# SCH_POTENCIA.net
KiCad netlist of a schematic drawn in Altium Designer
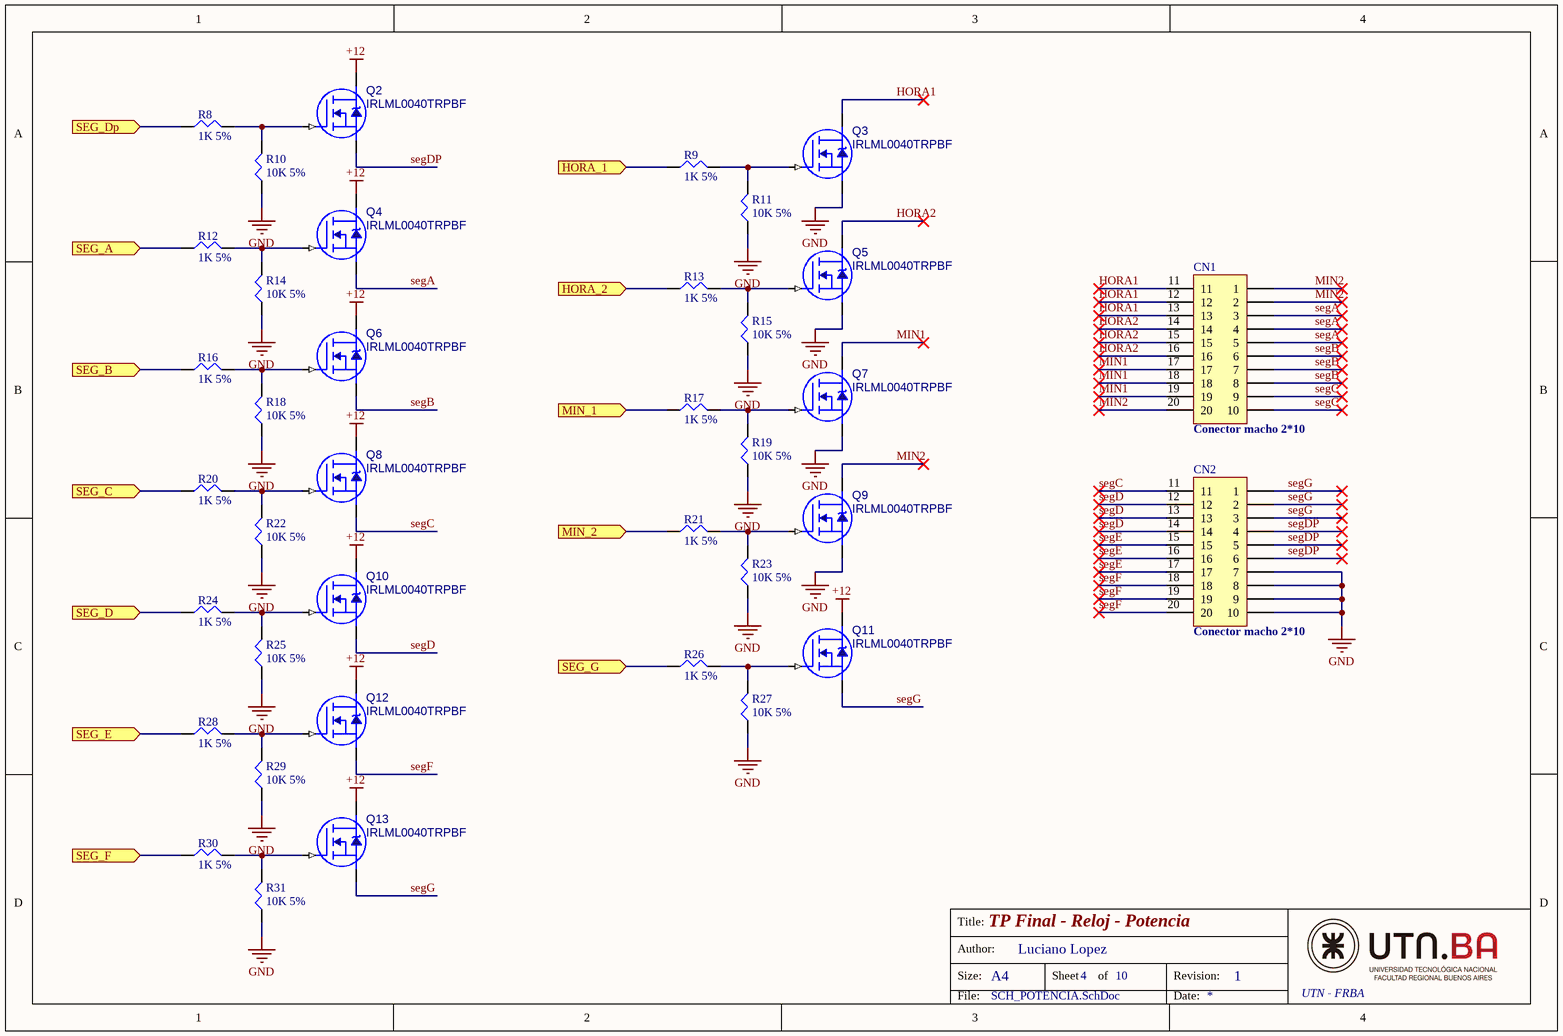
[diagram p0: SCH_POTENCIA.SchDoc]

(export (version "E")
  (design (tool "Eeschema 10.0.6"))
  (components
    (comp (ref "CN1")
      (value "Conector macho 2*10")
      (description "Connector Generic 10 Vias")
      (libsource (lib "SCH_LIB") (part "CONN_2x10P"))
    )
    (comp (ref "CN2")
      (value "Conector macho 2*10")
      (description "Connector Generic 10 Vias")
      (libsource (lib "SCH_LIB") (part "CONN_2x10P"))
    )
    (comp (ref "Q2")
      (value "IRLML0040TRPBF")
      (footprint "IC_SOT-23")
      (description "Mosfet N-Ch")
      (libsource (lib "SCH_LIB") (part "N_MOSFET_SOT23"))
    )
    (comp (ref "Q3")
      (value "IRLML0040TRPBF")
      (footprint "IC_SOT-23")
      (description "Mosfet N-Ch")
      (libsource (lib "SCH_LIB") (part "N_MOSFET_SOT23"))
    )
    (comp (ref "Q4")
      (value "IRLML0040TRPBF")
      (footprint "IC_SOT-23")
      (description "Mosfet N-Ch")
      (libsource (lib "SCH_LIB") (part "N_MOSFET_SOT23"))
    )
    (comp (ref "Q5")
      (value "IRLML0040TRPBF")
      (footprint "IC_SOT-23")
      (description "Mosfet N-Ch")
      (libsource (lib "SCH_LIB") (part "N_MOSFET_SOT23"))
    )
    (comp (ref "Q6")
      (value "IRLML0040TRPBF")
      (footprint "IC_SOT-23")
      (description "Mosfet N-Ch")
      (libsource (lib "SCH_LIB") (part "N_MOSFET_SOT23"))
    )
    (comp (ref "Q7")
      (value "IRLML0040TRPBF")
      (footprint "IC_SOT-23")
      (description "Mosfet N-Ch")
      (libsource (lib "SCH_LIB") (part "N_MOSFET_SOT23"))
    )
    (comp (ref "Q8")
      (value "IRLML0040TRPBF")
      (footprint "IC_SOT-23")
      (description "Mosfet N-Ch")
      (libsource (lib "SCH_LIB") (part "N_MOSFET_SOT23"))
    )
    (comp (ref "Q9")
      (value "IRLML0040TRPBF")
      (footprint "IC_SOT-23")
      (description "Mosfet N-Ch")
      (libsource (lib "SCH_LIB") (part "N_MOSFET_SOT23"))
    )
    (comp (ref "Q10")
      (value "IRLML0040TRPBF")
      (footprint "IC_SOT-23")
      (description "Mosfet N-Ch")
      (libsource (lib "SCH_LIB") (part "N_MOSFET_SOT23"))
    )
    (comp (ref "Q11")
      (value "IRLML0040TRPBF")
      (footprint "IC_SOT-23")
      (description "Mosfet N-Ch")
      (libsource (lib "SCH_LIB") (part "N_MOSFET_SOT23"))
    )
    (comp (ref "Q12")
      (value "IRLML0040TRPBF")
      (footprint "IC_SOT-23")
      (description "Mosfet N-Ch")
      (libsource (lib "SCH_LIB") (part "N_MOSFET_SOT23"))
    )
    (comp (ref "Q13")
      (value "IRLML0040TRPBF")
      (footprint "IC_SOT-23")
      (description "Mosfet N-Ch")
      (libsource (lib "SCH_LIB") (part "N_MOSFET_SOT23"))
    )
    (comp (ref "R8")
      (value "1K 5%")
      (footprint "R_0805")
      (libsource (lib "IDCI_WifiNode_2_R00") (part "Resistor"))
    )
    (comp (ref "R9")
      (value "1K 5%")
      (footprint "R_0805")
      (libsource (lib "IDCI_WifiNode_2_R00") (part "Resistor"))
    )
    (comp (ref "R10")
      (value "10K 5%")
      (footprint "R_0805")
      (libsource (lib "IDCI_WifiNode_2_R00") (part "Resistor"))
    )
    (comp (ref "R11")
      (value "10K 5%")
      (footprint "R_0805")
      (libsource (lib "IDCI_WifiNode_2_R00") (part "Resistor"))
    )
    (comp (ref "R12")
      (value "1K 5%")
      (footprint "R_0805")
      (libsource (lib "IDCI_WifiNode_2_R00") (part "Resistor"))
    )
    (comp (ref "R13")
      (value "1K 5%")
      (footprint "R_0805")
      (libsource (lib "IDCI_WifiNode_2_R00") (part "Resistor"))
    )
    (comp (ref "R14")
      (value "10K 5%")
      (footprint "R_0805")
      (libsource (lib "IDCI_WifiNode_2_R00") (part "Resistor"))
    )
    (comp (ref "R15")
      (value "10K 5%")
      (footprint "R_0805")
      (libsource (lib "IDCI_WifiNode_2_R00") (part "Resistor"))
    )
    (comp (ref "R16")
      (value "1K 5%")
      (footprint "R_0805")
      (libsource (lib "IDCI_WifiNode_2_R00") (part "Resistor"))
    )
    (comp (ref "R17")
      (value "1K 5%")
      (footprint "R_0805")
      (libsource (lib "IDCI_WifiNode_2_R00") (part "Resistor"))
    )
    (comp (ref "R18")
      (value "10K 5%")
      (footprint "R_0805")
      (libsource (lib "IDCI_WifiNode_2_R00") (part "Resistor"))
    )
    (comp (ref "R19")
      (value "10K 5%")
      (footprint "R_0805")
      (libsource (lib "IDCI_WifiNode_2_R00") (part "Resistor"))
    )
    (comp (ref "R20")
      (value "1K 5%")
      (footprint "R_0805")
      (libsource (lib "IDCI_WifiNode_2_R00") (part "Resistor"))
    )
    (comp (ref "R21")
      (value "1K 5%")
      (footprint "R_0805")
      (libsource (lib "IDCI_WifiNode_2_R00") (part "Resistor"))
    )
    (comp (ref "R22")
      (value "10K 5%")
      (footprint "R_0805")
      (libsource (lib "IDCI_WifiNode_2_R00") (part "Resistor"))
    )
    (comp (ref "R23")
      (value "10K 5%")
      (footprint "R_0805")
      (libsource (lib "IDCI_WifiNode_2_R00") (part "Resistor"))
    )
    (comp (ref "R24")
      (value "1K 5%")
      (footprint "R_0805")
      (libsource (lib "IDCI_WifiNode_2_R00") (part "Resistor"))
    )
    (comp (ref "R25")
      (value "10K 5%")
      (footprint "R_0805")
      (libsource (lib "IDCI_WifiNode_2_R00") (part "Resistor"))
    )
    (comp (ref "R26")
      (value "1K 5%")
      (footprint "R_0805")
      (libsource (lib "IDCI_WifiNode_2_R00") (part "Resistor"))
    )
    (comp (ref "R27")
      (value "10K 5%")
      (footprint "R_0805")
      (libsource (lib "IDCI_WifiNode_2_R00") (part "Resistor"))
    )
    (comp (ref "R28")
      (value "1K 5%")
      (footprint "R_0805")
      (libsource (lib "IDCI_WifiNode_2_R00") (part "Resistor"))
    )
    (comp (ref "R29")
      (value "10K 5%")
      (footprint "R_0805")
      (libsource (lib "IDCI_WifiNode_2_R00") (part "Resistor"))
    )
    (comp (ref "R30")
      (value "1K 5%")
      (footprint "R_0805")
      (libsource (lib "IDCI_WifiNode_2_R00") (part "Resistor"))
    )
    (comp (ref "R31")
      (value "10K 5%")
      (footprint "R_0805")
      (libsource (lib "IDCI_WifiNode_2_R00") (part "Resistor"))
    )
  )
  (nets
    (net (code "1") (name "+12") (class "Default")
      (node (ref "Q10") (pin "3") (pinfunction "DRAIN_3") (pintype "passive"))
      (node (ref "Q11") (pin "3") (pinfunction "DRAIN_3") (pintype "passive"))
      (node (ref "Q12") (pin "3") (pinfunction "DRAIN_3") (pintype "passive"))
      (node (ref "Q13") (pin "3") (pinfunction "DRAIN_3") (pintype "passive"))
      (node (ref "Q2") (pin "3") (pinfunction "DRAIN_3") (pintype "passive"))
      (node (ref "Q4") (pin "3") (pinfunction "DRAIN_3") (pintype "passive"))
      (node (ref "Q6") (pin "3") (pinfunction "DRAIN_3") (pintype "passive"))
      (node (ref "Q8") (pin "3") (pinfunction "DRAIN_3") (pintype "passive"))
    )
    (net (code "2") (name "/HORA1") (class "Default")
      (node (ref "CN1") (pin "11") (pinfunction "11_11") (pintype "passive"))
      (node (ref "CN1") (pin "12") (pinfunction "12_12") (pintype "passive"))
      (node (ref "CN1") (pin "13") (pinfunction "13_13") (pintype "passive"))
      (node (ref "Q3") (pin "3") (pinfunction "DRAIN_3") (pintype "passive"))
    )
    (net (code "3") (name "/HORA2") (class "Default")
      (node (ref "CN1") (pin "14") (pinfunction "14_14") (pintype "passive"))
      (node (ref "CN1") (pin "15") (pinfunction "15_15") (pintype "passive"))
      (node (ref "CN1") (pin "16") (pinfunction "16_16") (pintype "passive"))
      (node (ref "Q5") (pin "3") (pinfunction "DRAIN_3") (pintype "passive"))
    )
    (net (code "4") (name "/HORA_1") (class "Default")
      (node (ref "R9") (pin "1") (pinfunction "1_1") (pintype "passive"))
    )
    (net (code "5") (name "/HORA_2") (class "Default")
      (node (ref "R13") (pin "1") (pinfunction "1_1") (pintype "passive"))
    )
    (net (code "6") (name "/MIN1") (class "Default")
      (node (ref "CN1") (pin "17") (pinfunction "17_17") (pintype "passive"))
      (node (ref "CN1") (pin "18") (pinfunction "18_18") (pintype "passive"))
      (node (ref "CN1") (pin "19") (pinfunction "19_19") (pintype "passive"))
      (node (ref "Q7") (pin "3") (pinfunction "DRAIN_3") (pintype "passive"))
    )
    (net (code "7") (name "/MIN2") (class "Default")
      (node (ref "CN1") (pin "1") (pinfunction "1_1") (pintype "passive"))
      (node (ref "CN1") (pin "2") (pinfunction "2_2") (pintype "passive"))
      (node (ref "CN1") (pin "20") (pinfunction "20_20") (pintype "passive"))
      (node (ref "Q9") (pin "3") (pinfunction "DRAIN_3") (pintype "passive"))
    )
    (net (code "8") (name "/MIN_1") (class "Default")
      (node (ref "R17") (pin "1") (pinfunction "1_1") (pintype "passive"))
    )
    (net (code "9") (name "/MIN_2") (class "Default")
      (node (ref "R21") (pin "1") (pinfunction "1_1") (pintype "passive"))
    )
    (net (code "10") (name "/SEG_A") (class "Default")
      (node (ref "R12") (pin "1") (pinfunction "1_1") (pintype "passive"))
    )
    (net (code "11") (name "/SEG_B") (class "Default")
      (node (ref "R16") (pin "1") (pinfunction "1_1") (pintype "passive"))
    )
    (net (code "12") (name "/SEG_C") (class "Default")
      (node (ref "R20") (pin "1") (pinfunction "1_1") (pintype "passive"))
    )
    (net (code "13") (name "/SEG_D") (class "Default")
      (node (ref "R24") (pin "1") (pinfunction "1_1") (pintype "passive"))
    )
    (net (code "14") (name "/SEG_Dp") (class "Default")
      (node (ref "R8") (pin "1") (pinfunction "1_1") (pintype "passive"))
    )
    (net (code "15") (name "/SEG_E") (class "Default")
      (node (ref "R28") (pin "1") (pinfunction "1_1") (pintype "passive"))
    )
    (net (code "16") (name "/SEG_F") (class "Default")
      (node (ref "R30") (pin "1") (pinfunction "1_1") (pintype "passive"))
    )
    (net (code "17") (name "/SEG_G") (class "Default")
      (node (ref "R26") (pin "1") (pinfunction "1_1") (pintype "passive"))
    )
    (net (code "18") (name "/segA") (class "Default")
      (node (ref "CN1") (pin "3") (pinfunction "3_3") (pintype "passive"))
      (node (ref "CN1") (pin "4") (pinfunction "4_4") (pintype "passive"))
      (node (ref "CN1") (pin "5") (pinfunction "5_5") (pintype "passive"))
      (node (ref "Q4") (pin "2") (pinfunction "SOURCE_2") (pintype "passive"))
    )
    (net (code "19") (name "/segB") (class "Default")
      (node (ref "CN1") (pin "6") (pinfunction "6_6") (pintype "passive"))
      (node (ref "CN1") (pin "7") (pinfunction "7_7") (pintype "passive"))
      (node (ref "CN1") (pin "8") (pinfunction "8_8") (pintype "passive"))
      (node (ref "Q6") (pin "2") (pinfunction "SOURCE_2") (pintype "passive"))
    )
    (net (code "20") (name "/segC") (class "Default")
      (node (ref "CN1") (pin "10") (pinfunction "10_10") (pintype "passive"))
      (node (ref "CN1") (pin "9") (pinfunction "9_9") (pintype "passive"))
      (node (ref "CN2") (pin "11") (pinfunction "11_11") (pintype "passive"))
      (node (ref "Q8") (pin "2") (pinfunction "SOURCE_2") (pintype "passive"))
    )
    (net (code "21") (name "/segD") (class "Default")
      (node (ref "CN2") (pin "12") (pinfunction "12_12") (pintype "passive"))
      (node (ref "CN2") (pin "13") (pinfunction "13_13") (pintype "passive"))
      (node (ref "CN2") (pin "14") (pinfunction "14_14") (pintype "passive"))
      (node (ref "Q10") (pin "2") (pinfunction "SOURCE_2") (pintype "passive"))
    )
    (net (code "22") (name "/segDP") (class "Default")
      (node (ref "CN2") (pin "4") (pinfunction "4_4") (pintype "passive"))
      (node (ref "CN2") (pin "5") (pinfunction "5_5") (pintype "passive"))
      (node (ref "CN2") (pin "6") (pinfunction "6_6") (pintype "passive"))
      (node (ref "Q2") (pin "2") (pinfunction "SOURCE_2") (pintype "passive"))
    )
    (net (code "23") (name "/segE") (class "Default")
      (node (ref "CN2") (pin "15") (pinfunction "15_15") (pintype "passive"))
      (node (ref "CN2") (pin "16") (pinfunction "16_16") (pintype "passive"))
      (node (ref "CN2") (pin "17") (pinfunction "17_17") (pintype "passive"))
    )
    (net (code "24") (name "/segF") (class "Default")
      (node (ref "CN2") (pin "18") (pinfunction "18_18") (pintype "passive"))
      (node (ref "CN2") (pin "19") (pinfunction "19_19") (pintype "passive"))
      (node (ref "CN2") (pin "20") (pinfunction "20_20") (pintype "passive"))
      (node (ref "Q12") (pin "2") (pinfunction "SOURCE_2") (pintype "passive"))
    )
    (net (code "25") (name "/segG") (class "Default")
      (node (ref "CN2") (pin "1") (pinfunction "1_1") (pintype "passive"))
      (node (ref "CN2") (pin "2") (pinfunction "2_2") (pintype "passive"))
      (node (ref "CN2") (pin "3") (pinfunction "3_3") (pintype "passive"))
      (node (ref "Q11") (pin "2") (pinfunction "SOURCE_2") (pintype "passive"))
      (node (ref "Q13") (pin "2") (pinfunction "SOURCE_2") (pintype "passive"))
    )
    (net (code "26") (name "GND") (class "Default")
      (node (ref "CN2") (pin "10") (pinfunction "10_10") (pintype "passive"))
      (node (ref "CN2") (pin "7") (pinfunction "7_7") (pintype "passive"))
      (node (ref "CN2") (pin "8") (pinfunction "8_8") (pintype "passive"))
      (node (ref "CN2") (pin "9") (pinfunction "9_9") (pintype "passive"))
      (node (ref "Q3") (pin "2") (pinfunction "SOURCE_2") (pintype "passive"))
      (node (ref "Q5") (pin "2") (pinfunction "SOURCE_2") (pintype "passive"))
      (node (ref "Q7") (pin "2") (pinfunction "SOURCE_2") (pintype "passive"))
      (node (ref "Q9") (pin "2") (pinfunction "SOURCE_2") (pintype "passive"))
      (node (ref "R10") (pin "1") (pinfunction "1_1") (pintype "passive"))
      (node (ref "R11") (pin "1") (pinfunction "1_1") (pintype "passive"))
      (node (ref "R14") (pin "1") (pinfunction "1_1") (pintype "passive"))
      (node (ref "R15") (pin "1") (pinfunction "1_1") (pintype "passive"))
      (node (ref "R18") (pin "1") (pinfunction "1_1") (pintype "passive"))
      (node (ref "R19") (pin "1") (pinfunction "1_1") (pintype "passive"))
      (node (ref "R22") (pin "1") (pinfunction "1_1") (pintype "passive"))
      (node (ref "R23") (pin "1") (pinfunction "1_1") (pintype "passive"))
      (node (ref "R25") (pin "1") (pinfunction "1_1") (pintype "passive"))
      (node (ref "R27") (pin "1") (pinfunction "1_1") (pintype "passive"))
      (node (ref "R29") (pin "1") (pinfunction "1_1") (pintype "passive"))
      (node (ref "R31") (pin "1") (pinfunction "1_1") (pintype "passive"))
    )
    (net (code "27") (name "Net-(Q2-GATE)") (class "Default")
      (node (ref "Q2") (pin "1") (pinfunction "GATE_1") (pintype "input"))
      (node (ref "R10") (pin "2") (pinfunction "2_2") (pintype "passive"))
      (node (ref "R8") (pin "2") (pinfunction "2_2") (pintype "passive"))
    )
    (net (code "28") (name "Net-(Q3-GATE)") (class "Default")
      (node (ref "Q3") (pin "1") (pinfunction "GATE_1") (pintype "input"))
      (node (ref "R11") (pin "2") (pinfunction "2_2") (pintype "passive"))
      (node (ref "R9") (pin "2") (pinfunction "2_2") (pintype "passive"))
    )
    (net (code "29") (name "Net-(Q4-GATE)") (class "Default")
      (node (ref "Q4") (pin "1") (pinfunction "GATE_1") (pintype "input"))
      (node (ref "R12") (pin "2") (pinfunction "2_2") (pintype "passive"))
      (node (ref "R14") (pin "2") (pinfunction "2_2") (pintype "passive"))
    )
    (net (code "30") (name "Net-(Q5-GATE)") (class "Default")
      (node (ref "Q5") (pin "1") (pinfunction "GATE_1") (pintype "input"))
      (node (ref "R13") (pin "2") (pinfunction "2_2") (pintype "passive"))
      (node (ref "R15") (pin "2") (pinfunction "2_2") (pintype "passive"))
    )
    (net (code "31") (name "Net-(Q6-GATE)") (class "Default")
      (node (ref "Q6") (pin "1") (pinfunction "GATE_1") (pintype "input"))
      (node (ref "R16") (pin "2") (pinfunction "2_2") (pintype "passive"))
      (node (ref "R18") (pin "2") (pinfunction "2_2") (pintype "passive"))
    )
    (net (code "32") (name "Net-(Q7-GATE)") (class "Default")
      (node (ref "Q7") (pin "1") (pinfunction "GATE_1") (pintype "input"))
      (node (ref "R17") (pin "2") (pinfunction "2_2") (pintype "passive"))
      (node (ref "R19") (pin "2") (pinfunction "2_2") (pintype "passive"))
    )
    (net (code "33") (name "Net-(Q8-GATE)") (class "Default")
      (node (ref "Q8") (pin "1") (pinfunction "GATE_1") (pintype "input"))
      (node (ref "R20") (pin "2") (pinfunction "2_2") (pintype "passive"))
      (node (ref "R22") (pin "2") (pinfunction "2_2") (pintype "passive"))
    )
    (net (code "34") (name "Net-(Q9-GATE)") (class "Default")
      (node (ref "Q9") (pin "1") (pinfunction "GATE_1") (pintype "input"))
      (node (ref "R21") (pin "2") (pinfunction "2_2") (pintype "passive"))
      (node (ref "R23") (pin "2") (pinfunction "2_2") (pintype "passive"))
    )
    (net (code "35") (name "Net-(Q10-GATE)") (class "Default")
      (node (ref "Q10") (pin "1") (pinfunction "GATE_1") (pintype "input"))
      (node (ref "R24") (pin "2") (pinfunction "2_2") (pintype "passive"))
      (node (ref "R25") (pin "2") (pinfunction "2_2") (pintype "passive"))
    )
    (net (code "36") (name "Net-(Q11-GATE)") (class "Default")
      (node (ref "Q11") (pin "1") (pinfunction "GATE_1") (pintype "input"))
      (node (ref "R26") (pin "2") (pinfunction "2_2") (pintype "passive"))
      (node (ref "R27") (pin "2") (pinfunction "2_2") (pintype "passive"))
    )
    (net (code "37") (name "Net-(Q12-GATE)") (class "Default")
      (node (ref "Q12") (pin "1") (pinfunction "GATE_1") (pintype "input"))
      (node (ref "R28") (pin "2") (pinfunction "2_2") (pintype "passive"))
      (node (ref "R29") (pin "2") (pinfunction "2_2") (pintype "passive"))
    )
    (net (code "38") (name "Net-(Q13-GATE)") (class "Default")
      (node (ref "Q13") (pin "1") (pinfunction "GATE_1") (pintype "input"))
      (node (ref "R30") (pin "2") (pinfunction "2_2") (pintype "passive"))
      (node (ref "R31") (pin "2") (pinfunction "2_2") (pintype "passive"))
    )
  )
)
